# blinky.net
KiCad netlist of a schematic drawn in EAGLE
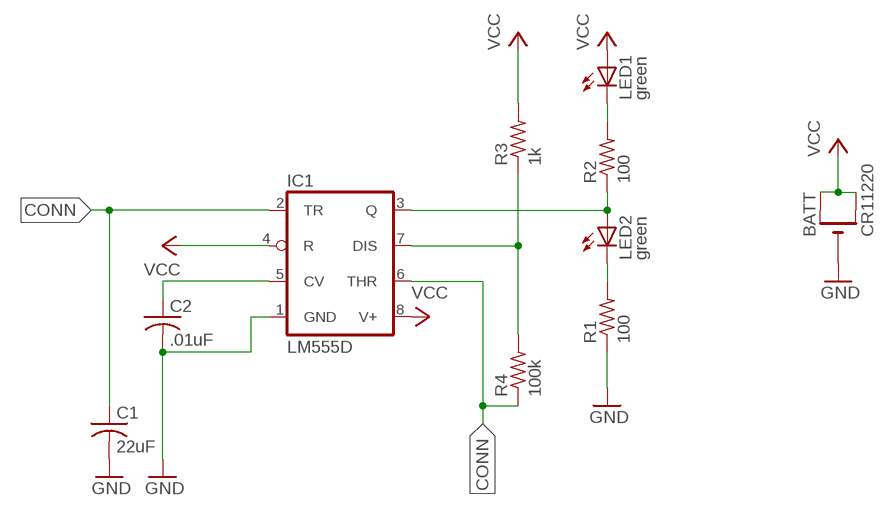
[diagram p0: schematic, sheet 1]

(export (version "E")
  (design (tool "Eeschema 10.0.6"))
  (components
    (comp (ref "BATT")
      (value "CR11220")
      (footprint "eagle-import:CR1220-SMD")
      (libsource (lib "eagle-import") (part "CR1220SMT"))
    )
    (comp (ref "C1")
      (value "22uF")
      (footprint "eagle-import:C0805")
      (libsource (lib "eagle-import") (part "C-USC0805"))
    )
    (comp (ref "C2")
      (value ".01uF")
      (footprint "eagle-import:C0805")
      (libsource (lib "eagle-import") (part "C-USC0805"))
    )
    (comp (ref "IC1")
      (value "LM555D")
      (footprint "eagle-import:SO08")
      (libsource (lib "eagle-import") (part "555DLM"))
    )
    (comp (ref "LED1")
      (value "green")
      (footprint "eagle-import:CHIPLED_0805")
      (libsource (lib "eagle-import") (part "LEDCHIPLED_0805"))
    )
    (comp (ref "LED2")
      (value "green")
      (footprint "eagle-import:CHIPLED_0805")
      (libsource (lib "eagle-import") (part "LEDCHIPLED_0805"))
    )
    (comp (ref "R1")
      (value "100")
      (footprint "eagle-import:R0805")
      (libsource (lib "eagle-import") (part "R-US_R0805"))
    )
    (comp (ref "R2")
      (value "100")
      (footprint "eagle-import:R0805")
      (libsource (lib "eagle-import") (part "R-US_R0805"))
    )
    (comp (ref "R3")
      (value "1k")
      (footprint "eagle-import:R0805")
      (libsource (lib "eagle-import") (part "R-US_R0805"))
    )
    (comp (ref "R4")
      (value "100k")
      (footprint "eagle-import:R0805")
      (libsource (lib "eagle-import") (part "R-US_R0805"))
    )
  )
  (nets
    (net (code "1") (name "CONN") (class "Default")
      (node (ref "C1") (pin "1") (pinfunction "1_1") (pintype "passive"))
      (node (ref "IC1") (pin "2") (pinfunction "TR_2") (pintype "input"))
      (node (ref "IC1") (pin "6") (pinfunction "THR_6") (pintype "input"))
      (node (ref "R4") (pin "1") (pinfunction "1_1") (pintype "passive"))
    )
    (net (code "2") (name "GND") (class "Default")
      (node (ref "BATT") (pin "-") (pinfunction "-_-") (pintype "passive"))
      (node (ref "C1") (pin "2") (pinfunction "2_2") (pintype "passive"))
      (node (ref "C2") (pin "2") (pinfunction "2_2") (pintype "passive"))
      (node (ref "IC1") (pin "1") (pinfunction "GND_1") (pintype "power_in"))
      (node (ref "R1") (pin "1") (pinfunction "1_1") (pintype "passive"))
    )
    (net (code "3") (name "Net-(IC1-CV)") (class "Default")
      (node (ref "C2") (pin "1") (pinfunction "1_1") (pintype "passive"))
      (node (ref "IC1") (pin "5") (pinfunction "CV_5") (pintype "input"))
    )
    (net (code "4") (name "Net-(IC1-DIS)") (class "Default")
      (node (ref "IC1") (pin "7") (pinfunction "DIS_7") (pintype "input"))
      (node (ref "R3") (pin "1") (pinfunction "1_1") (pintype "passive"))
      (node (ref "R4") (pin "2") (pinfunction "2_2") (pintype "passive"))
    )
    (net (code "5") (name "Net-(IC1-Q)") (class "Default")
      (node (ref "IC1") (pin "3") (pinfunction "Q_3") (pintype "output"))
      (node (ref "LED2") (pin "A") (pinfunction "A_A") (pintype "passive"))
      (node (ref "R2") (pin "1") (pinfunction "1_1") (pintype "passive"))
    )
    (net (code "6") (name "Net-(LED1-PadC)") (class "Default")
      (node (ref "LED1") (pin "C") (pinfunction "C_C") (pintype "passive"))
      (node (ref "R2") (pin "2") (pinfunction "2_2") (pintype "passive"))
    )
    (net (code "7") (name "Net-(LED2-PadC)") (class "Default")
      (node (ref "LED2") (pin "C") (pinfunction "C_C") (pintype "passive"))
      (node (ref "R1") (pin "2") (pinfunction "2_2") (pintype "passive"))
    )
    (net (code "8") (name "VCC") (class "Default")
      (node (ref "BATT") (pin "+$1") (pinfunction "+_+$1") (pintype "passive"))
      (node (ref "BATT") (pin "+$2") (pinfunction "+1_+$2") (pintype "passive"))
      (node (ref "IC1") (pin "4") (pinfunction "R_4") (pintype "input"))
      (node (ref "IC1") (pin "8") (pinfunction "V+_8") (pintype "power_in"))
      (node (ref "LED1") (pin "A") (pinfunction "A_A") (pintype "passive"))
      (node (ref "R3") (pin "2") (pinfunction "2_2") (pintype "passive"))
    )
  )
)
